# SAMD21.net
KiCad netlist of a schematic drawn in EAGLE
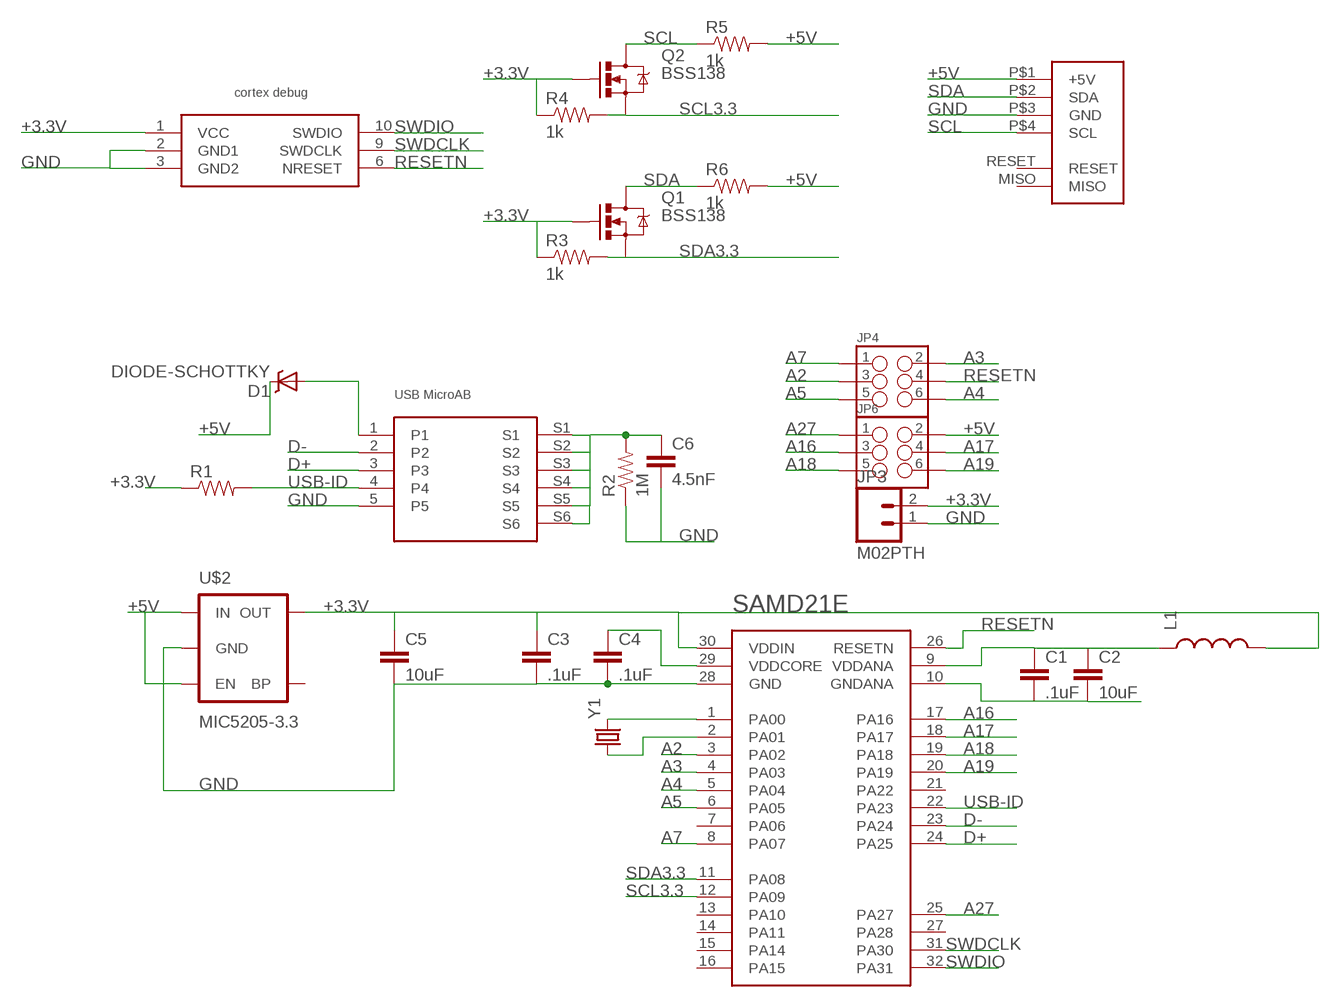
[diagram p0: schematic, sheet 1]

(export (version "E")
  (design (tool "Eeschema 10.0.6"))
  (components
    (comp (ref "C1")
      (value ".1uF")
      (footprint "eagle-import:0805")
      (libsource (lib "eagle-import") (part "CAP0805"))
    )
    (comp (ref "C2")
      (value "10uF")
      (footprint "eagle-import:0805")
      (libsource (lib "eagle-import") (part "CAP0805"))
    )
    (comp (ref "C3")
      (value ".1uF")
      (footprint "eagle-import:0805")
      (libsource (lib "eagle-import") (part "CAP0805"))
    )
    (comp (ref "C4")
      (value ".1uF")
      (footprint "eagle-import:0805")
      (libsource (lib "eagle-import") (part "CAP0805"))
    )
    (comp (ref "C5")
      (value "10uF")
      (footprint "eagle-import:0805")
      (libsource (lib "eagle-import") (part "CAP0805"))
    )
    (comp (ref "C6")
      (value "4.5nF")
      (footprint "eagle-import:0805")
      (libsource (lib "eagle-import") (part "CAP0805"))
    )
    (comp (ref "D1")
      (value "DIODE-SCHOTTKY")
      (footprint "eagle-import:SOD-523")
      (libsource (lib "eagle-import") (part "DIODE-SCHOTTKY"))
    )
    (comp (ref "JP3")
      (value "M02PTH")
      (footprint "eagle-import:1X02")
      (libsource (lib "eagle-import") (part "M02PTH"))
    )
    (comp (ref "JP4")
      (value "M03X22X3_SILK_SM")
      (footprint "eagle-import:2X3")
      (libsource (lib "eagle-import") (part "M03X22X3_SILK_SM"))
    )
    (comp (ref "JP6")
      (value "M03X22X3_SILK_SM")
      (footprint "eagle-import:2X3")
      (libsource (lib "eagle-import") (part "M03X22X3_SILK_SM"))
    )
    (comp (ref "L1")
      (value "INDUCTOR0805")
      (footprint "eagle-import:0805")
      (libsource (lib "eagle-import") (part "INDUCTOR0805"))
    )
    (comp (ref "Q1")
      (value "BSS138")
      (footprint "eagle-import:SOT23")
      (libsource (lib "eagle-import") (part "MOSFET-NCHANNELBSS138"))
    )
    (comp (ref "Q2")
      (value "BSS138")
      (footprint "eagle-import:SOT23")
      (libsource (lib "eagle-import") (part "MOSFET-NCHANNELBSS138"))
    )
    (comp (ref "R1")
      (value "RESISTOR0805-RES")
      (footprint "eagle-import:0805")
      (libsource (lib "eagle-import") (part "RESISTOR0805-RES"))
    )
    (comp (ref "R2")
      (value "1M")
      (footprint "eagle-import:0805")
      (libsource (lib "eagle-import") (part "RESISTOR0805-RES"))
    )
    (comp (ref "R3")
      (value "1k")
      (footprint "eagle-import:0805")
      (libsource (lib "eagle-import") (part "RESISTOR0805-RES"))
    )
    (comp (ref "R4")
      (value "1k")
      (footprint "eagle-import:0805")
      (libsource (lib "eagle-import") (part "RESISTOR0805-RES"))
    )
    (comp (ref "R5")
      (value "1k")
      (footprint "eagle-import:0805")
      (libsource (lib "eagle-import") (part "RESISTOR0805-RES"))
    )
    (comp (ref "R6")
      (value "1k")
      (footprint "eagle-import:0805")
      (libsource (lib "eagle-import") (part "RESISTOR0805-RES"))
    )
    (comp (ref "U$1")
      (value "SAMD21E")
      (footprint "eagle-import:TQFP-32")
      (libsource (lib "eagle-import") (part "SAMD21E"))
    )
    (comp (ref "U$2")
      (value "MIC5205-3.3")
      (footprint "eagle-import:SOT23-5")
      (libsource (lib "eagle-import") (part "V_REG_MIC52053.3V"))
    )
    (comp (ref "U$3")
      (value "USB-MICRO-AB")
      (footprint "eagle-import:MOLEX-MICROAB")
      (libsource (lib "eagle-import") (part "USB-MICRO-AB"))
    )
    (comp (ref "U$4")
      (value "FOOTPRINT")
      (footprint "eagle-import:FOOTPRINT")
      (libsource (lib "eagle-import") (part "FOOTPRINT"))
    )
    (comp (ref "U$5")
      (value "CORTEX-DEBUG")
      (footprint "eagle-import:HEADER-10-.05")
      (libsource (lib "eagle-import") (part "CORTEX-DEBUG"))
    )
    (comp (ref "Y1")
      (value "CRYSTALTXC-7A")
      (footprint "eagle-import:CRYSTAL-TXC-7A")
      (libsource (lib "eagle-import") (part "CRYSTALTXC-7A"))
    )
  )
  (nets
    (net (code "1") (name "/+3.3V") (class "Default")
      (node (ref "C3") (pin "1") (pinfunction "1_1") (pintype "passive"))
      (node (ref "C5") (pin "1") (pinfunction "1_1") (pintype "passive"))
      (node (ref "JP3") (pin "2") (pinfunction "2_2") (pintype "passive"))
      (node (ref "L1") (pin "2") (pinfunction "2_2") (pintype "passive"))
      (node (ref "Q1") (pin "1") (pinfunction "G_1") (pintype "passive"))
      (node (ref "Q2") (pin "1") (pinfunction "G_1") (pintype "passive"))
      (node (ref "R1") (pin "1") (pinfunction "1_1") (pintype "passive"))
      (node (ref "R3") (pin "1") (pinfunction "1_1") (pintype "passive"))
      (node (ref "R4") (pin "1") (pinfunction "1_1") (pintype "passive"))
      (node (ref "U$1") (pin "30") (pinfunction "VDDIN_30") (pintype "bidirectional"))
      (node (ref "U$2") (pin "5") (pinfunction "OUT_5") (pintype "passive"))
      (node (ref "U$5") (pin "1") (pinfunction "VCC_1") (pintype "bidirectional"))
    )
    (net (code "2") (name "/+5V") (class "Default")
      (node (ref "D1") (pin "C") (pinfunction "C_C") (pintype "passive"))
      (node (ref "JP6") (pin "2") (pinfunction "2_2") (pintype "bidirectional"))
      (node (ref "R5") (pin "2") (pinfunction "2_2") (pintype "passive"))
      (node (ref "R6") (pin "2") (pinfunction "2_2") (pintype "passive"))
      (node (ref "U$2") (pin "1") (pinfunction "IN_1") (pintype "input"))
      (node (ref "U$2") (pin "3") (pinfunction "EN_3") (pintype "input"))
      (node (ref "U$4") (pin "P$1") (pinfunction "+5V_P$1") (pintype "power_in"))
    )
    (net (code "3") (name "/A2") (class "Default")
      (node (ref "JP4") (pin "3") (pinfunction "3_3") (pintype "bidirectional"))
      (node (ref "U$1") (pin "3") (pinfunction "PA02_3") (pintype "bidirectional"))
    )
    (net (code "4") (name "/A3") (class "Default")
      (node (ref "JP4") (pin "2") (pinfunction "2_2") (pintype "bidirectional"))
      (node (ref "U$1") (pin "4") (pinfunction "PA03_4") (pintype "bidirectional"))
    )
    (net (code "5") (name "/A4") (class "Default")
      (node (ref "JP4") (pin "6") (pinfunction "6_6") (pintype "bidirectional"))
      (node (ref "U$1") (pin "5") (pinfunction "PA04_5") (pintype "bidirectional"))
    )
    (net (code "6") (name "/A5") (class "Default")
      (node (ref "JP4") (pin "5") (pinfunction "5_5") (pintype "bidirectional"))
      (node (ref "U$1") (pin "6") (pinfunction "PA05_6") (pintype "bidirectional"))
    )
    (net (code "7") (name "/A7") (class "Default")
      (node (ref "JP4") (pin "1") (pinfunction "1_1") (pintype "bidirectional"))
      (node (ref "U$1") (pin "8") (pinfunction "PA07_8") (pintype "bidirectional"))
    )
    (net (code "8") (name "/A16") (class "Default")
      (node (ref "JP6") (pin "3") (pinfunction "3_3") (pintype "bidirectional"))
      (node (ref "U$1") (pin "17") (pinfunction "PA16_17") (pintype "bidirectional"))
    )
    (net (code "9") (name "/A17") (class "Default")
      (node (ref "JP6") (pin "4") (pinfunction "4_4") (pintype "bidirectional"))
      (node (ref "U$1") (pin "18") (pinfunction "PA17_18") (pintype "bidirectional"))
    )
    (net (code "10") (name "/A18") (class "Default")
      (node (ref "JP6") (pin "5") (pinfunction "5_5") (pintype "bidirectional"))
      (node (ref "U$1") (pin "19") (pinfunction "PA18_19") (pintype "bidirectional"))
    )
    (net (code "11") (name "/A19") (class "Default")
      (node (ref "JP6") (pin "6") (pinfunction "6_6") (pintype "bidirectional"))
      (node (ref "U$1") (pin "20") (pinfunction "PA19_20") (pintype "bidirectional"))
    )
    (net (code "12") (name "/A27") (class "Default")
      (node (ref "JP6") (pin "1") (pinfunction "1_1") (pintype "bidirectional"))
      (node (ref "U$1") (pin "25") (pinfunction "PA27_25") (pintype "bidirectional"))
    )
    (net (code "13") (name "/D+") (class "Default")
      (node (ref "U$1") (pin "24") (pinfunction "PA25_24") (pintype "bidirectional"))
      (node (ref "U$3") (pin "3") (pinfunction "P3_3") (pintype "bidirectional"))
    )
    (net (code "14") (name "/D-") (class "Default")
      (node (ref "U$1") (pin "23") (pinfunction "PA24_23") (pintype "bidirectional"))
      (node (ref "U$3") (pin "2") (pinfunction "P2_2") (pintype "bidirectional"))
    )
    (net (code "15") (name "/GND") (class "Default")
      (node (ref "C3") (pin "2") (pinfunction "2_2") (pintype "passive"))
      (node (ref "C4") (pin "2") (pinfunction "2_2") (pintype "passive"))
      (node (ref "C5") (pin "2") (pinfunction "2_2") (pintype "passive"))
      (node (ref "C6") (pin "2") (pinfunction "2_2") (pintype "passive"))
      (node (ref "JP3") (pin "1") (pinfunction "1_1") (pintype "passive"))
      (node (ref "R2") (pin "1") (pinfunction "1_1") (pintype "passive"))
      (node (ref "U$1") (pin "28") (pinfunction "GND_28") (pintype "bidirectional"))
      (node (ref "U$2") (pin "2") (pinfunction "GND_2") (pintype "input"))
      (node (ref "U$3") (pin "5") (pinfunction "P5_5") (pintype "bidirectional"))
      (node (ref "U$4") (pin "P$3") (pinfunction "GND_P$3") (pintype "power_in"))
      (node (ref "U$5") (pin "2") (pinfunction "GND1_2") (pintype "bidirectional"))
      (node (ref "U$5") (pin "3") (pinfunction "GND2_3") (pintype "bidirectional"))
    )
    (net (code "16") (name "/RESETN") (class "Default")
      (node (ref "JP4") (pin "4") (pinfunction "4_4") (pintype "bidirectional"))
      (node (ref "U$1") (pin "26") (pinfunction "RESETN_26") (pintype "bidirectional"))
      (node (ref "U$5") (pin "6") (pinfunction "NRESET_6") (pintype "bidirectional"))
    )
    (net (code "17") (name "/SCL") (class "Default")
      (node (ref "Q2") (pin "3") (pinfunction "D_3") (pintype "passive"))
      (node (ref "R5") (pin "1") (pinfunction "1_1") (pintype "passive"))
      (node (ref "U$4") (pin "P$4") (pinfunction "SCL_P$4") (pintype "bidirectional"))
    )
    (net (code "18") (name "/SCL3.3") (class "Default")
      (node (ref "Q2") (pin "2") (pinfunction "S_2") (pintype "passive"))
      (node (ref "R4") (pin "2") (pinfunction "2_2") (pintype "passive"))
      (node (ref "U$1") (pin "12") (pinfunction "PA09_12") (pintype "bidirectional"))
    )
    (net (code "19") (name "/SDA") (class "Default")
      (node (ref "Q1") (pin "3") (pinfunction "D_3") (pintype "passive"))
      (node (ref "R6") (pin "1") (pinfunction "1_1") (pintype "passive"))
      (node (ref "U$4") (pin "P$2") (pinfunction "SDA_P$2") (pintype "bidirectional"))
    )
    (net (code "20") (name "/SDA3.3") (class "Default")
      (node (ref "Q1") (pin "2") (pinfunction "S_2") (pintype "passive"))
      (node (ref "R3") (pin "2") (pinfunction "2_2") (pintype "passive"))
      (node (ref "U$1") (pin "11") (pinfunction "PA08_11") (pintype "bidirectional"))
    )
    (net (code "21") (name "/SWDCLK") (class "Default")
      (node (ref "U$1") (pin "31") (pinfunction "PA30_31") (pintype "bidirectional"))
      (node (ref "U$5") (pin "9") (pinfunction "SWDCLK_9") (pintype "bidirectional"))
    )
    (net (code "22") (name "/SWDIO") (class "Default")
      (node (ref "U$1") (pin "32") (pinfunction "PA31_32") (pintype "bidirectional"))
      (node (ref "U$5") (pin "10") (pinfunction "SWDIO_10") (pintype "bidirectional"))
    )
    (net (code "23") (name "/USB-ID") (class "Default")
      (node (ref "R1") (pin "2") (pinfunction "2_2") (pintype "passive"))
      (node (ref "U$1") (pin "22") (pinfunction "PA23_22") (pintype "bidirectional"))
      (node (ref "U$3") (pin "4") (pinfunction "P4_4") (pintype "bidirectional"))
    )
    (net (code "24") (name "Net-(C6-Pad1)") (class "Default")
      (node (ref "C6") (pin "1") (pinfunction "1_1") (pintype "passive"))
      (node (ref "R2") (pin "2") (pinfunction "2_2") (pintype "passive"))
      (node (ref "U$3") (pin "S1") (pinfunction "S1_S1") (pintype "bidirectional"))
      (node (ref "U$3") (pin "S2") (pinfunction "S2_S2") (pintype "bidirectional"))
      (node (ref "U$3") (pin "S3") (pinfunction "S3_S3") (pintype "bidirectional"))
      (node (ref "U$3") (pin "S4") (pinfunction "S4_S4") (pintype "bidirectional"))
      (node (ref "U$3") (pin "S5") (pinfunction "S5_S5") (pintype "bidirectional"))
      (node (ref "U$3") (pin "S6") (pinfunction "S6_S6") (pintype "bidirectional"))
    )
    (net (code "25") (name "Net-(U$1-GNDANA)") (class "Default")
      (node (ref "C1") (pin "2") (pinfunction "2_2") (pintype "passive"))
      (node (ref "C2") (pin "2") (pinfunction "2_2") (pintype "passive"))
      (node (ref "U$1") (pin "10") (pinfunction "GNDANA_10") (pintype "bidirectional"))
    )
    (net (code "26") (name "Net-(U$1-PA00)") (class "Default")
      (node (ref "U$1") (pin "1") (pinfunction "PA00_1") (pintype "bidirectional"))
      (node (ref "Y1") (pin "P$2") (pinfunction "2_P$2") (pintype "passive"))
    )
    (net (code "27") (name "Net-(U$1-PA01)") (class "Default")
      (node (ref "U$1") (pin "2") (pinfunction "PA01_2") (pintype "bidirectional"))
      (node (ref "Y1") (pin "P$1") (pinfunction "1_P$1") (pintype "passive"))
    )
    (net (code "28") (name "Net-(U$1-VDDANA)") (class "Default")
      (node (ref "C1") (pin "1") (pinfunction "1_1") (pintype "passive"))
      (node (ref "C2") (pin "1") (pinfunction "1_1") (pintype "passive"))
      (node (ref "L1") (pin "1") (pinfunction "1_1") (pintype "passive"))
      (node (ref "U$1") (pin "9") (pinfunction "VDDANA_9") (pintype "bidirectional"))
    )
    (net (code "29") (name "Net-(U$1-VDDCORE)") (class "Default")
      (node (ref "C4") (pin "1") (pinfunction "1_1") (pintype "passive"))
      (node (ref "U$1") (pin "29") (pinfunction "VDDCORE_29") (pintype "bidirectional"))
    )
    (net (code "30") (name "Net-(U$3-P1)") (class "Default")
      (node (ref "D1") (pin "A") (pinfunction "A_A") (pintype "passive"))
      (node (ref "U$3") (pin "1") (pinfunction "P1_1") (pintype "bidirectional"))
    )
    (net (code "31") (name "unconnected-(U$1-PA06-Pad7)") (class "Default")
      (node (ref "U$1") (pin "7") (pinfunction "PA06_7") (pintype "bidirectional"))
    )
    (net (code "32") (name "unconnected-(U$1-PA10-Pad13)") (class "Default")
      (node (ref "U$1") (pin "13") (pinfunction "PA10_13") (pintype "bidirectional"))
    )
    (net (code "33") (name "unconnected-(U$1-PA11-Pad14)") (class "Default")
      (node (ref "U$1") (pin "14") (pinfunction "PA11_14") (pintype "bidirectional"))
    )
    (net (code "34") (name "unconnected-(U$1-PA14-Pad15)") (class "Default")
      (node (ref "U$1") (pin "15") (pinfunction "PA14_15") (pintype "bidirectional"))
    )
    (net (code "35") (name "unconnected-(U$1-PA15-Pad16)") (class "Default")
      (node (ref "U$1") (pin "16") (pinfunction "PA15_16") (pintype "bidirectional"))
    )
    (net (code "36") (name "unconnected-(U$1-PA22-Pad21)") (class "Default")
      (node (ref "U$1") (pin "21") (pinfunction "PA22_21") (pintype "bidirectional"))
    )
    (net (code "37") (name "unconnected-(U$1-PA28-Pad27)") (class "Default")
      (node (ref "U$1") (pin "27") (pinfunction "PA28_27") (pintype "bidirectional"))
    )
    (net (code "38") (name "unconnected-(U$2-BP-Pad4)") (class "Default")
      (node (ref "U$2") (pin "4") (pinfunction "BP_4") (pintype "input"))
    )
    (net (code "39") (name "unconnected-(U$4-PadMISO)") (class "Default")
      (node (ref "U$4") (pin "MISO") (pinfunction "MISO_MISO") (pintype "bidirectional"))
    )
    (net (code "40") (name "unconnected-(U$4-PadRESET)") (class "Default")
      (node (ref "U$4") (pin "RESET") (pinfunction "RESET_RESET") (pintype "bidirectional"))
    )
  )
)
